# ScreamFilter.net
KiCad netlist of a schematic drawn in EAGLE
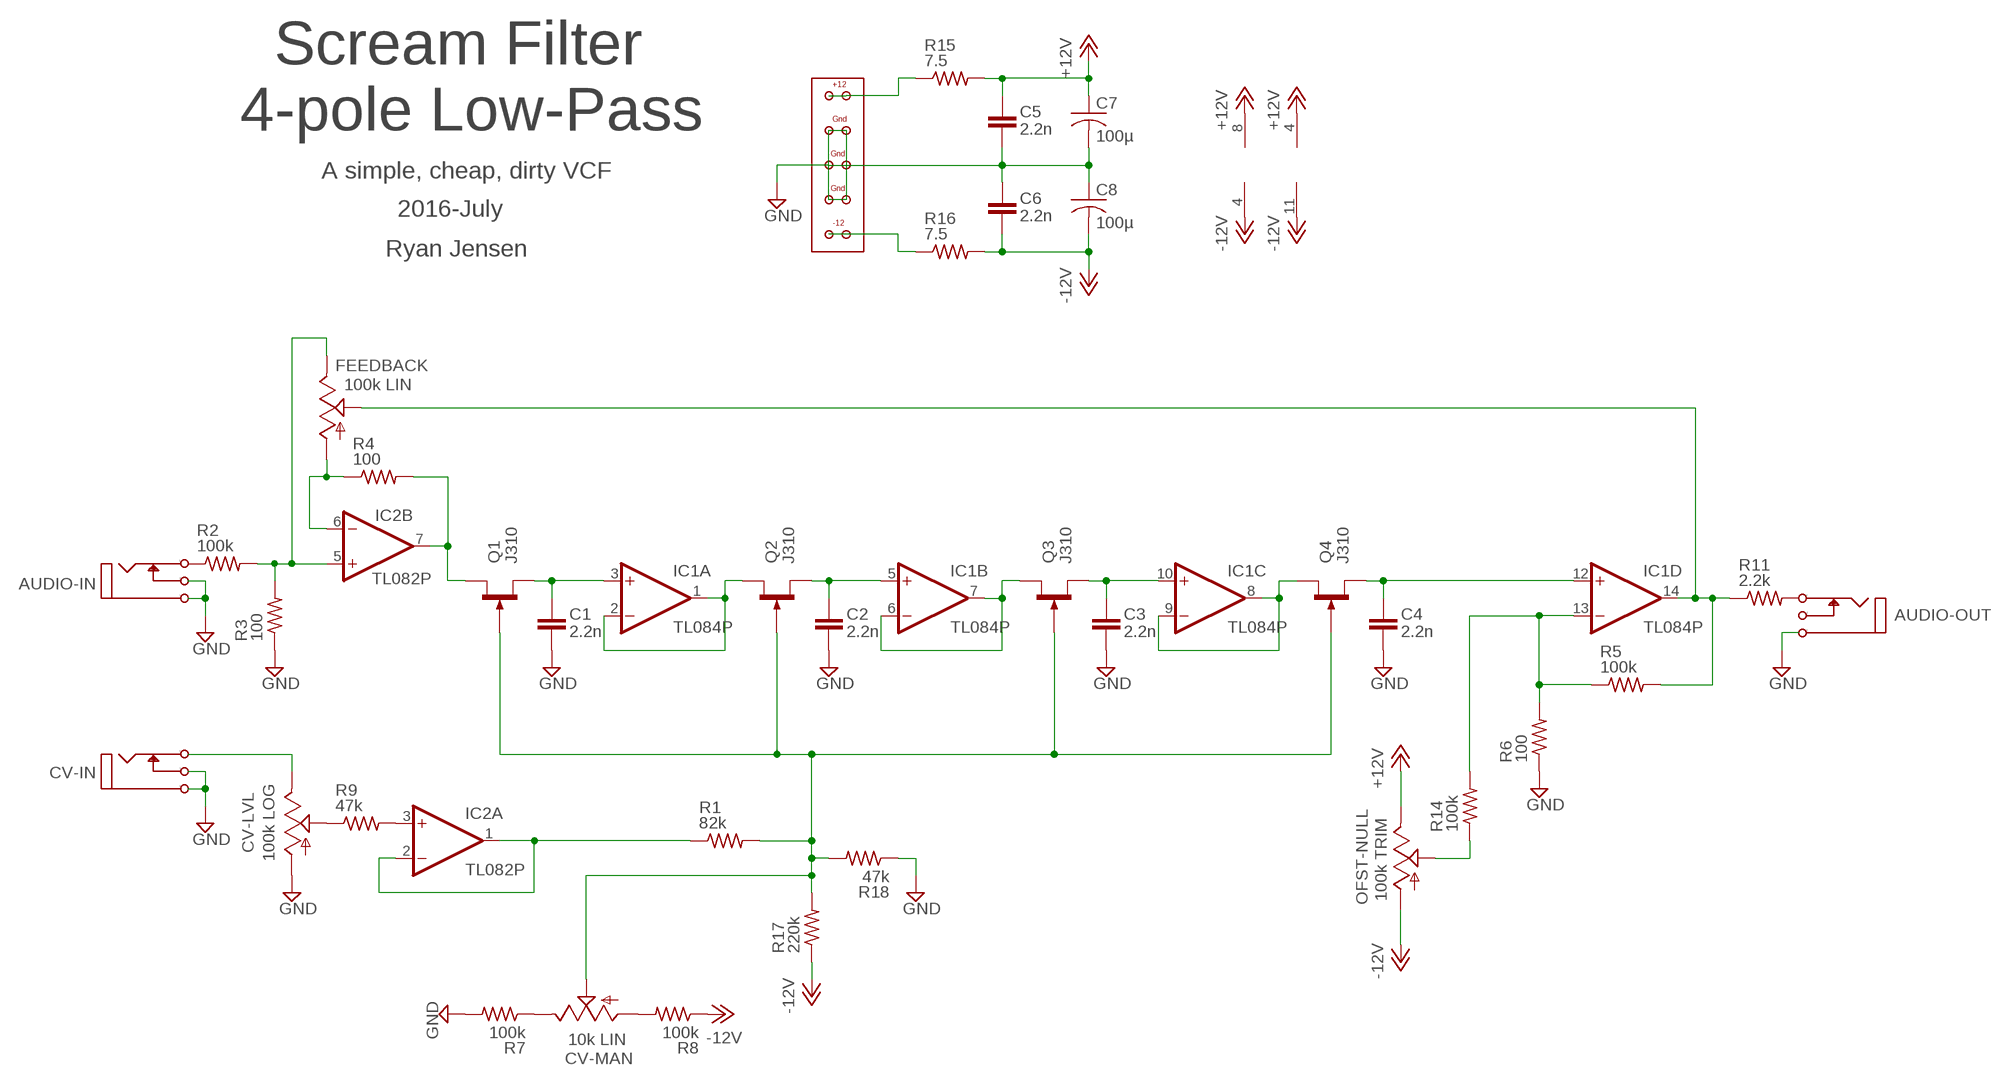
[diagram p0: schematic, sheet 1]

(export (version "E")
  (design (tool "Eeschema 10.0.6"))
  (components
    (comp (ref "AUDIO-IN")
      (value "I/O")
      (footprint "eagle-import:MONO_JACK")
      (libsource (lib "eagle-import") (part "MONO_JACK"))
    )
    (comp (ref "AUDIO-OUT")
      (value "I/O")
      (footprint "eagle-import:MONO_JACK")
      (libsource (lib "eagle-import") (part "MONO_JACK"))
    )
    (comp (ref "C1")
      (value "2.2n")
      (footprint "eagle-import:C025-025X050")
      (libsource (lib "eagle-import") (part "C-EU025-025X050"))
    )
    (comp (ref "C2")
      (value "2.2n")
      (footprint "eagle-import:C025-025X050")
      (libsource (lib "eagle-import") (part "C-EU025-025X050"))
    )
    (comp (ref "C3")
      (value "2.2n")
      (footprint "eagle-import:C025-025X050")
      (libsource (lib "eagle-import") (part "C-EU025-025X050"))
    )
    (comp (ref "C4")
      (value "2.2n")
      (footprint "eagle-import:C025-025X050")
      (libsource (lib "eagle-import") (part "C-EU025-025X050"))
    )
    (comp (ref "C5")
      (value "2.2n")
      (footprint "eagle-import:C025-025X050")
      (libsource (lib "eagle-import") (part "C-EU025-025X050"))
    )
    (comp (ref "C6")
      (value "2.2n")
      (footprint "eagle-import:C025-025X050")
      (libsource (lib "eagle-import") (part "C-EU025-025X050"))
    )
    (comp (ref "C7")
      (value "100µ")
      (footprint "eagle-import:C025-050X050")
      (libsource (lib "eagle-import") (part "C-US025-050X050"))
    )
    (comp (ref "C8")
      (value "100µ")
      (footprint "eagle-import:C025-050X050")
      (libsource (lib "eagle-import") (part "C-US025-050X050"))
    )
    (comp (ref "CV-IN")
      (value "I/O")
      (footprint "eagle-import:MONO_JACK")
      (libsource (lib "eagle-import") (part "MONO_JACK"))
    )
    (comp (ref "CV-LVL")
      (value "100k LOG")
      (footprint "eagle-import:B64Y")
      (libsource (lib "eagle-import") (part "TRIM_US-B64Y"))
    )
    (comp (ref "CV-MAN")
      (value "10k LIN")
      (footprint "eagle-import:B64Y")
      (libsource (lib "eagle-import") (part "TRIM_US-B64Y"))
    )
    (comp (ref "FEEDBACK")
      (value "100k LIN")
      (footprint "eagle-import:B64Y")
      (libsource (lib "eagle-import") (part "TRIM_US-B64Y"))
    )
    (comp (ref "IC1")
      (value "TL084P")
      (footprint "eagle-import:DIL14")
      (libsource (lib "eagle-import") (part "TL084P"))
    )
    (comp (ref "IC2")
      (value "TL082P")
      (footprint "eagle-import:DIL08")
      (libsource (lib "eagle-import") (part "TL082P"))
    )
    (comp (ref "OFST-NULL")
      (value "100k TRIM")
      (footprint "eagle-import:B64Y")
      (libsource (lib "eagle-import") (part "TRIM_US-B64Y"))
    )
    (comp (ref "Q1")
      (value "J310")
      (footprint "eagle-import:TO92R")
      (libsource (lib "eagle-import") (part "J310"))
    )
    (comp (ref "Q2")
      (value "J310")
      (footprint "eagle-import:TO92R")
      (libsource (lib "eagle-import") (part "J310"))
    )
    (comp (ref "Q3")
      (value "J310")
      (footprint "eagle-import:TO92R")
      (libsource (lib "eagle-import") (part "J310"))
    )
    (comp (ref "Q4")
      (value "J310")
      (footprint "eagle-import:TO92R")
      (libsource (lib "eagle-import") (part "J310"))
    )
    (comp (ref "R1")
      (value "82k")
      (footprint "eagle-import:0204_7")
      (libsource (lib "eagle-import") (part "R-US_0204/7"))
    )
    (comp (ref "R2")
      (value "100k")
      (footprint "eagle-import:0204_7")
      (libsource (lib "eagle-import") (part "R-US_0204/7"))
    )
    (comp (ref "R3")
      (value "100")
      (footprint "eagle-import:0204_7")
      (libsource (lib "eagle-import") (part "R-US_0204/7"))
    )
    (comp (ref "R4")
      (value "100")
      (footprint "eagle-import:0204_7")
      (libsource (lib "eagle-import") (part "R-US_0204/7"))
    )
    (comp (ref "R5")
      (value "100k")
      (footprint "eagle-import:0204_7")
      (libsource (lib "eagle-import") (part "R-US_0204/7"))
    )
    (comp (ref "R6")
      (value "100")
      (footprint "eagle-import:0204_7")
      (libsource (lib "eagle-import") (part "R-US_0204/7"))
    )
    (comp (ref "R7")
      (value "100k")
      (footprint "eagle-import:0204_7")
      (libsource (lib "eagle-import") (part "R-US_0204/7"))
    )
    (comp (ref "R8")
      (value "100k")
      (footprint "eagle-import:0204_7")
      (libsource (lib "eagle-import") (part "R-US_0204/7"))
    )
    (comp (ref "R9")
      (value "47k")
      (footprint "eagle-import:0204_7")
      (libsource (lib "eagle-import") (part "R-US_0204/7"))
    )
    (comp (ref "R11")
      (value "2.2k")
      (footprint "eagle-import:0204_7")
      (libsource (lib "eagle-import") (part "R-US_0204/7"))
    )
    (comp (ref "R14")
      (value "100k")
      (footprint "eagle-import:0204_7")
      (libsource (lib "eagle-import") (part "R-US_0204/7"))
    )
    (comp (ref "R15")
      (value "7.5")
      (footprint "eagle-import:0204_7")
      (libsource (lib "eagle-import") (part "R-US_0204/7"))
    )
    (comp (ref "R16")
      (value "7.5")
      (footprint "eagle-import:0204_7")
      (libsource (lib "eagle-import") (part "R-US_0204/7"))
    )
    (comp (ref "R17")
      (value "220k")
      (footprint "eagle-import:0204_7")
      (libsource (lib "eagle-import") (part "R-US_0204/7"))
    )
    (comp (ref "R18")
      (value "47k")
      (footprint "eagle-import:0204_7")
      (libsource (lib "eagle-import") (part "R-US_0204/7"))
    )
    (comp (ref "U$1")
      (value "EURORACK-POWER")
      (footprint "eagle-import:EURORACK-POWER")
      (libsource (lib "eagle-import") (part "EURORACK-POWER"))
    )
  )
  (nets
    (net (code "1") (name "+12V") (class "Default")
      (node (ref "C5") (pin "1") (pinfunction "1_1") (pintype "passive"))
      (node (ref "C7") (pin "1") (pinfunction "1_1") (pintype "passive"))
      (node (ref "IC1") (pin "4") (pinfunction "V+_4") (pintype "power_in"))
      (node (ref "IC2") (pin "8") (pinfunction "V+_8") (pintype "power_in"))
      (node (ref "OFST-NULL") (pin "E") (pinfunction "E_E") (pintype "passive"))
      (node (ref "R15") (pin "2") (pinfunction "2_2") (pintype "passive"))
    )
    (net (code "2") (name "-12V") (class "Default")
      (node (ref "C6") (pin "2") (pinfunction "2_2") (pintype "passive"))
      (node (ref "C8") (pin "2") (pinfunction "2_2") (pintype "passive"))
      (node (ref "IC1") (pin "11") (pinfunction "V-_11") (pintype "power_in"))
      (node (ref "IC2") (pin "4") (pinfunction "V-_4") (pintype "power_in"))
      (node (ref "OFST-NULL") (pin "A") (pinfunction "A_A") (pintype "passive"))
      (node (ref "R16") (pin "2") (pinfunction "2_2") (pintype "passive"))
      (node (ref "R17") (pin "1") (pinfunction "1_1") (pintype "passive"))
      (node (ref "R8") (pin "1") (pinfunction "1_1") (pintype "passive"))
    )
    (net (code "3") (name "GND") (class "Default")
      (node (ref "AUDIO-IN") (pin "P$1") (pinfunction "P$1_P$1") (pintype "bidirectional"))
      (node (ref "AUDIO-IN") (pin "P$3") (pinfunction "P3_P$3") (pintype "bidirectional"))
      (node (ref "AUDIO-OUT") (pin "P$1") (pinfunction "P$1_P$1") (pintype "bidirectional"))
      (node (ref "C1") (pin "2") (pinfunction "2_2") (pintype "passive"))
      (node (ref "C2") (pin "2") (pinfunction "2_2") (pintype "passive"))
      (node (ref "C3") (pin "2") (pinfunction "2_2") (pintype "passive"))
      (node (ref "C4") (pin "2") (pinfunction "2_2") (pintype "passive"))
      (node (ref "C5") (pin "2") (pinfunction "2_2") (pintype "passive"))
      (node (ref "C6") (pin "1") (pinfunction "1_1") (pintype "passive"))
      (node (ref "C7") (pin "2") (pinfunction "2_2") (pintype "passive"))
      (node (ref "C8") (pin "1") (pinfunction "1_1") (pintype "passive"))
      (node (ref "CV-IN") (pin "P$1") (pinfunction "P$1_P$1") (pintype "bidirectional"))
      (node (ref "CV-IN") (pin "P$3") (pinfunction "P3_P$3") (pintype "bidirectional"))
      (node (ref "CV-LVL") (pin "A") (pinfunction "A_A") (pintype "passive"))
      (node (ref "R18") (pin "1") (pinfunction "1_1") (pintype "passive"))
      (node (ref "R3") (pin "1") (pinfunction "1_1") (pintype "passive"))
      (node (ref "R6") (pin "1") (pinfunction "1_1") (pintype "passive"))
      (node (ref "R7") (pin "2") (pinfunction "2_2") (pintype "passive"))
      (node (ref "U$1") (pin "P$3") (pinfunction "P$3_P$3") (pintype "bidirectional"))
      (node (ref "U$1") (pin "P$4") (pinfunction "P$4_P$4") (pintype "bidirectional"))
      (node (ref "U$1") (pin "P$5") (pinfunction "P$5_P$5") (pintype "bidirectional"))
      (node (ref "U$1") (pin "P$6") (pinfunction "P$6_P$6") (pintype "bidirectional"))
      (node (ref "U$1") (pin "P$7") (pinfunction "P$7_P$7") (pintype "bidirectional"))
      (node (ref "U$1") (pin "P$8") (pinfunction "P$8_P$8") (pintype "bidirectional"))
    )
    (net (code "4") (name "Net-(AUDIO-IN-P2)") (class "Default")
      (node (ref "AUDIO-IN") (pin "P$2") (pinfunction "P2_P$2") (pintype "bidirectional"))
      (node (ref "R2") (pin "1") (pinfunction "1_1") (pintype "passive"))
    )
    (net (code "5") (name "Net-(AUDIO-OUT-P2)") (class "Default")
      (node (ref "AUDIO-OUT") (pin "P$2") (pinfunction "P2_P$2") (pintype "bidirectional"))
      (node (ref "R11") (pin "2") (pinfunction "2_2") (pintype "passive"))
    )
    (net (code "6") (name "Net-(CV-IN-P2)") (class "Default")
      (node (ref "CV-IN") (pin "P$2") (pinfunction "P2_P$2") (pintype "bidirectional"))
      (node (ref "CV-LVL") (pin "E") (pinfunction "E_E") (pintype "passive"))
    )
    (net (code "7") (name "Net-(CV-LVL-PadS)") (class "Default")
      (node (ref "CV-LVL") (pin "S") (pinfunction "S_S") (pintype "passive"))
      (node (ref "R9") (pin "1") (pinfunction "1_1") (pintype "passive"))
    )
    (net (code "8") (name "Net-(CV-MAN-PadA)") (class "Default")
      (node (ref "CV-MAN") (pin "A") (pinfunction "A_A") (pintype "passive"))
      (node (ref "R8") (pin "2") (pinfunction "2_2") (pintype "passive"))
    )
    (net (code "9") (name "Net-(CV-MAN-PadE)") (class "Default")
      (node (ref "CV-MAN") (pin "E") (pinfunction "E_E") (pintype "passive"))
      (node (ref "R7") (pin "1") (pinfunction "1_1") (pintype "passive"))
    )
    (net (code "10") (name "Net-(CV-MAN-PadS)") (class "Default")
      (node (ref "CV-MAN") (pin "S") (pinfunction "S_S") (pintype "passive"))
      (node (ref "Q1") (pin "G") (pinfunction "G_G") (pintype "passive"))
      (node (ref "Q2") (pin "G") (pinfunction "G_G") (pintype "passive"))
      (node (ref "Q3") (pin "G") (pinfunction "G_G") (pintype "passive"))
      (node (ref "Q4") (pin "G") (pinfunction "G_G") (pintype "passive"))
      (node (ref "R1") (pin "2") (pinfunction "2_2") (pintype "passive"))
      (node (ref "R17") (pin "2") (pinfunction "2_2") (pintype "passive"))
      (node (ref "R18") (pin "2") (pinfunction "2_2") (pintype "passive"))
    )
    (net (code "11") (name "Net-(IC1A-+IN)") (class "Default")
      (node (ref "C1") (pin "1") (pinfunction "1_1") (pintype "passive"))
      (node (ref "IC1") (pin "3") (pinfunction "+IN_3") (pintype "input"))
      (node (ref "Q1") (pin "S") (pinfunction "S_S") (pintype "passive"))
    )
    (net (code "12") (name "Net-(IC1A--IN)") (class "Default")
      (node (ref "IC1") (pin "1") (pinfunction "OUT_1") (pintype "output"))
      (node (ref "IC1") (pin "2") (pinfunction "-IN_2") (pintype "input"))
      (node (ref "Q2") (pin "D") (pinfunction "D_D") (pintype "passive"))
    )
    (net (code "13") (name "Net-(IC1B-+IN)") (class "Default")
      (node (ref "C2") (pin "1") (pinfunction "1_1") (pintype "passive"))
      (node (ref "IC1") (pin "5") (pinfunction "+IN_5") (pintype "input"))
      (node (ref "Q2") (pin "S") (pinfunction "S_S") (pintype "passive"))
    )
    (net (code "14") (name "Net-(IC1B--IN)") (class "Default")
      (node (ref "IC1") (pin "6") (pinfunction "-IN_6") (pintype "input"))
      (node (ref "IC1") (pin "7") (pinfunction "OUT_7") (pintype "output"))
      (node (ref "Q3") (pin "D") (pinfunction "D_D") (pintype "passive"))
    )
    (net (code "15") (name "Net-(IC1C-+IN)") (class "Default")
      (node (ref "C3") (pin "1") (pinfunction "1_1") (pintype "passive"))
      (node (ref "IC1") (pin "10") (pinfunction "+IN_10") (pintype "input"))
      (node (ref "Q3") (pin "S") (pinfunction "S_S") (pintype "passive"))
    )
    (net (code "16") (name "Net-(IC1C--IN)") (class "Default")
      (node (ref "IC1") (pin "8") (pinfunction "OUT_8") (pintype "output"))
      (node (ref "IC1") (pin "9") (pinfunction "-IN_9") (pintype "input"))
      (node (ref "Q4") (pin "D") (pinfunction "D_D") (pintype "passive"))
    )
    (net (code "17") (name "Net-(IC1D-+IN)") (class "Default")
      (node (ref "C4") (pin "1") (pinfunction "1_1") (pintype "passive"))
      (node (ref "IC1") (pin "12") (pinfunction "+IN_12") (pintype "input"))
      (node (ref "Q4") (pin "S") (pinfunction "S_S") (pintype "passive"))
    )
    (net (code "18") (name "Net-(IC1D--IN)") (class "Default")
      (node (ref "IC1") (pin "13") (pinfunction "-IN_13") (pintype "input"))
      (node (ref "R14") (pin "2") (pinfunction "2_2") (pintype "passive"))
      (node (ref "R5") (pin "1") (pinfunction "1_1") (pintype "passive"))
      (node (ref "R6") (pin "2") (pinfunction "2_2") (pintype "passive"))
    )
    (net (code "19") (name "Net-(IC1D-OUT)") (class "Default")
      (node (ref "FEEDBACK") (pin "S") (pinfunction "S_S") (pintype "passive"))
      (node (ref "IC1") (pin "14") (pinfunction "OUT_14") (pintype "output"))
      (node (ref "R11") (pin "1") (pinfunction "1_1") (pintype "passive"))
      (node (ref "R5") (pin "2") (pinfunction "2_2") (pintype "passive"))
    )
    (net (code "20") (name "Net-(IC2A-+IN)") (class "Default")
      (node (ref "IC2") (pin "3") (pinfunction "+IN_3") (pintype "input"))
      (node (ref "R9") (pin "2") (pinfunction "2_2") (pintype "passive"))
    )
    (net (code "21") (name "Net-(IC2A--IN)") (class "Default")
      (node (ref "IC2") (pin "1") (pinfunction "OUT_1") (pintype "output"))
      (node (ref "IC2") (pin "2") (pinfunction "-IN_2") (pintype "input"))
      (node (ref "R1") (pin "1") (pinfunction "1_1") (pintype "passive"))
    )
    (net (code "22") (name "Net-(IC2B-+IN)") (class "Default")
      (node (ref "FEEDBACK") (pin "E") (pinfunction "E_E") (pintype "passive"))
      (node (ref "IC2") (pin "5") (pinfunction "+IN_5") (pintype "input"))
      (node (ref "R2") (pin "2") (pinfunction "2_2") (pintype "passive"))
      (node (ref "R3") (pin "2") (pinfunction "2_2") (pintype "passive"))
    )
    (net (code "23") (name "Net-(IC2B--IN)") (class "Default")
      (node (ref "FEEDBACK") (pin "A") (pinfunction "A_A") (pintype "passive"))
      (node (ref "IC2") (pin "6") (pinfunction "-IN_6") (pintype "input"))
      (node (ref "R4") (pin "1") (pinfunction "1_1") (pintype "passive"))
    )
    (net (code "24") (name "Net-(IC2B-OUT)") (class "Default")
      (node (ref "IC2") (pin "7") (pinfunction "OUT_7") (pintype "output"))
      (node (ref "Q1") (pin "D") (pinfunction "D_D") (pintype "passive"))
      (node (ref "R4") (pin "2") (pinfunction "2_2") (pintype "passive"))
    )
    (net (code "25") (name "Net-(OFST-NULL-PadS)") (class "Default")
      (node (ref "OFST-NULL") (pin "S") (pinfunction "S_S") (pintype "passive"))
      (node (ref "R14") (pin "1") (pinfunction "1_1") (pintype "passive"))
    )
    (net (code "26") (name "Net-(R15-Pad1)") (class "Default")
      (node (ref "R15") (pin "1") (pinfunction "1_1") (pintype "passive"))
      (node (ref "U$1") (pin "P$1") (pinfunction "P$1_P$1") (pintype "bidirectional"))
      (node (ref "U$1") (pin "P$2") (pinfunction "P$2_P$2") (pintype "bidirectional"))
    )
    (net (code "27") (name "Net-(R16-Pad1)") (class "Default")
      (node (ref "R16") (pin "1") (pinfunction "1_1") (pintype "passive"))
      (node (ref "U$1") (pin "P$10") (pinfunction "P$10_P$10") (pintype "bidirectional"))
      (node (ref "U$1") (pin "P$9") (pinfunction "P$9_P$9") (pintype "bidirectional"))
    )
    (net (code "28") (name "unconnected-(AUDIO-OUT-P3-PadP$3)") (class "Default")
      (node (ref "AUDIO-OUT") (pin "P$3") (pinfunction "P3_P$3") (pintype "bidirectional"))
    )
  )
)
